# DCDC_2_Rev2.net
KiCad netlist of a schematic drawn in Altium Designer
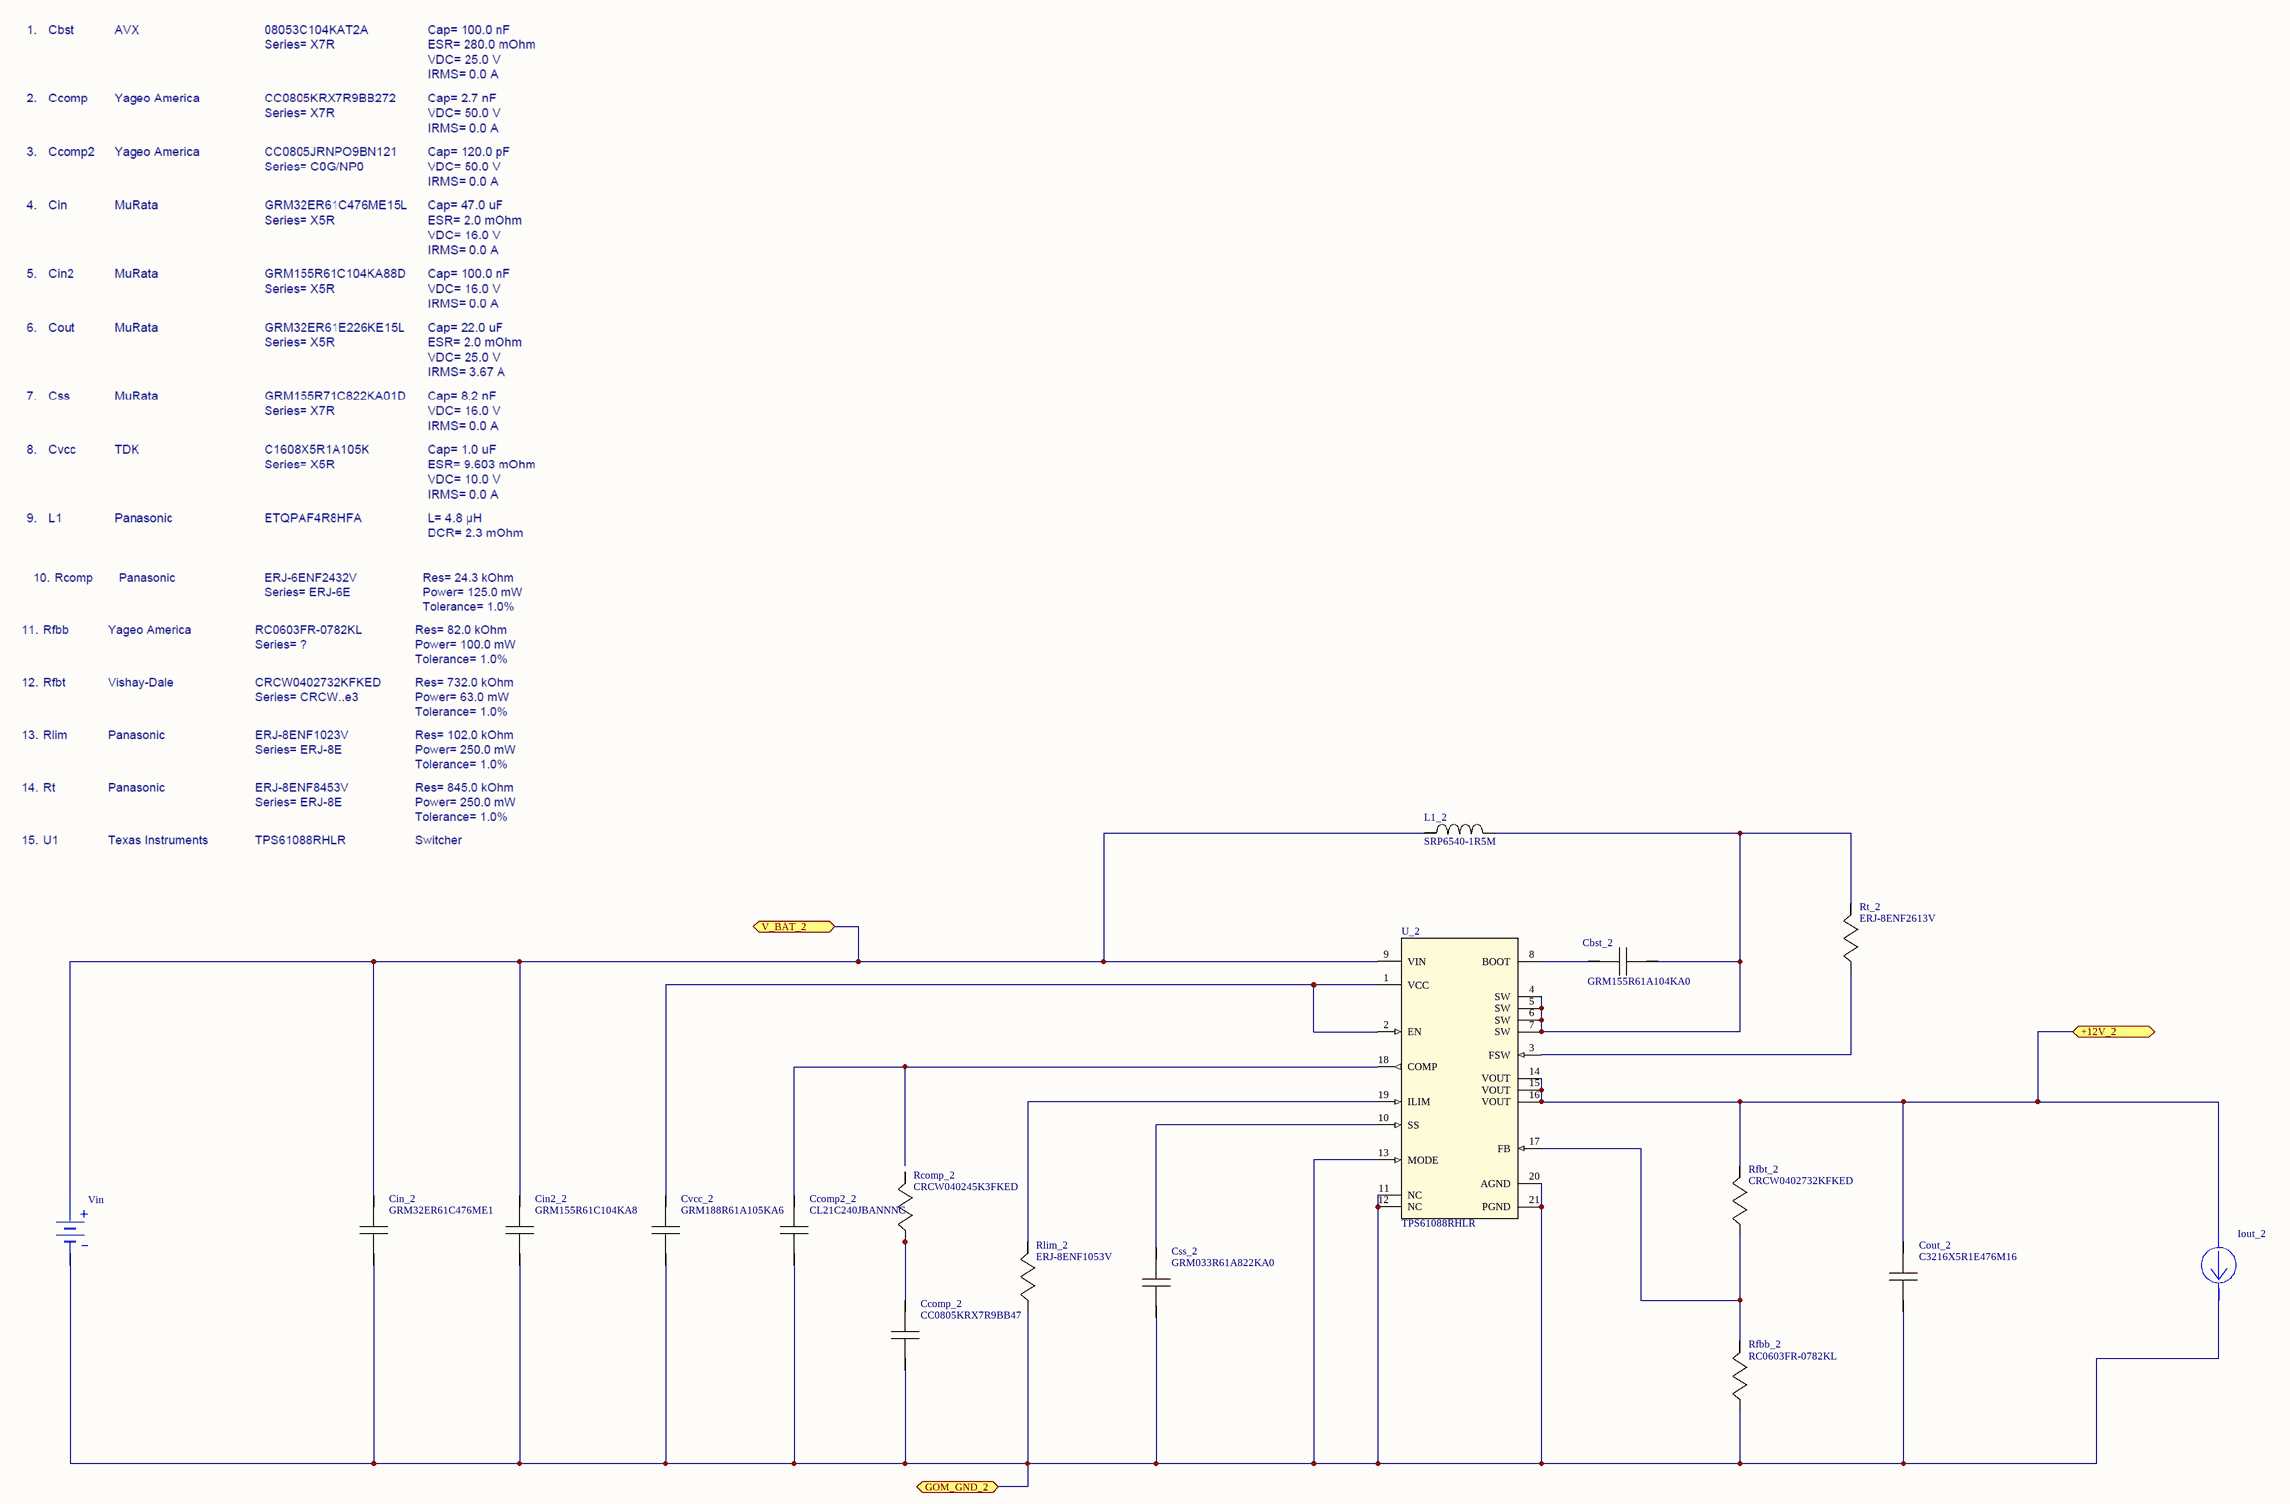
[diagram p0: DCDC_2_Rev2.SchDoc]

(export (version "E")
  (design (tool "Eeschema 10.0.6"))
  (components
    (comp (ref "Cbst_2")
      (value "GRM155R61A104KA0")
      (footprint "0402")
      (description "Imported")
      (fields (field (name "MANUFACTURER_PART_NUMBER") "GRM155R61A104KA01D"))
      (libsource (lib "2016-03-14_16-10-16") (part "GRM155R61A104KA0"))
    )
    (comp (ref "Ccomp2_2")
      (value "CL21C240JBANNNC")
      (footprint "0805")
      (description "Imported")
      (libsource (lib "2016-03-14_16-10-16") (part "CL21C240JBANNNC"))
    )
    (comp (ref "Ccomp_2")
      (value "CC0805KRX7R9BB47")
      (footprint "0805")
      (description "Imported")
      (fields (field (name "MANUFACTURER_PART_NUMBER") "CC0805KRX7R9BB471"))
      (libsource (lib "2016-03-14_16-10-16") (part "CC0805KRX7R9BB47"))
    )
    (comp (ref "Cin2_2")
      (value "GRM155R61C104KA8")
      (footprint "0402")
      (description "Imported")
      (fields (field (name "MANUFACTURER_PART_NUMBER") "GRM155R61C104KA88D"))
      (libsource (lib "2016-03-14_16-10-16") (part "GRM155R61C104KA8"))
    )
    (comp (ref "Cin_2")
      (value "GRM32ER61C476ME1")
      (footprint "1210_280")
      (description "Imported")
      (fields (field (name "MANUFACTURER_PART_NUMBER") "GRM32ER61C476ME15L"))
      (libsource (lib "2016-03-14_16-10-16") (part "GRM32ER61C476ME1"))
    )
    (comp (ref "Cout_2")
      (value "C3216X5R1E476M16")
      (footprint "1206_190")
      (description "Imported")
      (fields (field (name "MANUFACTURER_PART_NUMBER") "C3216X5R1E476M160AC"))
      (libsource (lib "2016-03-14_16-10-16") (part "C3216X5R1E476M16"))
    )
    (comp (ref "Css_2")
      (value "GRM033R61A822KA0")
      (footprint "0201")
      (description "Imported")
      (fields (field (name "MANUFACTURER_PART_NUMBER") "GRM033R61A822KA01D"))
      (libsource (lib "2016-03-14_16-10-16") (part "GRM033R61A822KA0"))
    )
    (comp (ref "Cvcc_2")
      (value "GRM188R61A105KA6")
      (footprint "0603")
      (description "Imported")
      (fields (field (name "MANUFACTURER_PART_NUMBER") "GRM188R61A105KA61D"))
      (libsource (lib "2016-03-14_16-10-16") (part "GRM188R61A105KA6"))
    )
    (comp (ref "Iout_2") (value "WB_CURRENT_LOAD") (libsource (lib "TI WEBENCH") (part "Iout")))
    (comp (ref "L1_2")
      (value "SRP6540-1R5M")
      (footprint "SRP6540")
      (description "Imported")
      (fields (field (name "MANUFACTURER") "Bourns"))
      (libsource (lib "2016-03-14_16-10-16") (part "SRP6540-1R5M"))
    )
    (comp (ref "Rcomp_2")
      (value "CRCW040245K3FKED")
      (footprint "0402")
      (description "Imported")
      (libsource (lib "2016-03-14_16-10-16") (part "CRCW040245K3FKED"))
    )
    (comp (ref "Rfbb_2")
      (value "RC0603FR-0782KL")
      (footprint "0603")
      (description "Imported")
      (libsource (lib "2016-03-14_16-10-16") (part "RC0603FR-0782KL"))
    )
    (comp (ref "Rfbt_2")
      (value "CRCW0402732KFKED")
      (footprint "0402")
      (description "Imported")
      (libsource (lib "2016-03-14_16-10-16") (part "CRCW0402732KFKED"))
    )
    (comp (ref "Rlim_2")
      (value "ERJ-8ENF1053V")
      (footprint "1206")
      (description "Imported")
      (libsource (lib "2016-03-14_16-10-16") (part "ERJ-8ENF1053V"))
    )
    (comp (ref "Rt_2")
      (value "ERJ-8ENF2613V")
      (footprint "1206")
      (description "Imported")
      (libsource (lib "2016-03-14_16-10-16") (part "ERJ-8ENF2613V"))
    )
    (comp (ref "U_2")
      (value "TPS61088RHLR")
      (footprint "RHL0020A")
      (description "Imported")
      (fields
        (field (name "ALTERNATE PARTNUMBER") "TPS61088RHLT")
        (field (name "MANUFACTURER") "Texas Instruments")
      )
      (libsource (lib "2016-03-14_16-10-16") (part "TPS61088RHLR"))
    )
    (comp (ref "Vin") (value "WB_BATTERY") (libsource (lib "TI WEBENCH") (part "Vin")))
  )
  (nets
    (net (code "1") (name "/+12V_2") (class "Default")
      (node (ref "Cout_2") (pin "1") (pinfunction "1_1") (pintype "passive"))
      (node (ref "Iout_2") (pin "1") (pinfunction "+_1") (pintype "passive"))
      (node (ref "Rfbt_2") (pin "1") (pinfunction "1_1") (pintype "passive"))
      (node (ref "U_2") (pin "14") (pinfunction "VOUT_14") (pintype "power_in"))
      (node (ref "U_2") (pin "15") (pinfunction "VOUT_15") (pintype "power_in"))
      (node (ref "U_2") (pin "16") (pinfunction "VOUT_16") (pintype "power_in"))
    )
    (net (code "2") (name "/GOM_GND_2") (class "Default")
      (node (ref "Ccomp2_2") (pin "2") (pinfunction "2_2") (pintype "passive"))
      (node (ref "Ccomp_2") (pin "2") (pinfunction "2_2") (pintype "passive"))
      (node (ref "Cin2_2") (pin "2") (pinfunction "2_2") (pintype "passive"))
      (node (ref "Cin_2") (pin "2") (pinfunction "2_2") (pintype "passive"))
      (node (ref "Cout_2") (pin "2") (pinfunction "2_2") (pintype "passive"))
      (node (ref "Css_2") (pin "2") (pinfunction "2_2") (pintype "passive"))
      (node (ref "Cvcc_2") (pin "2") (pinfunction "2_2") (pintype "passive"))
      (node (ref "Iout_2") (pin "2") (pinfunction "-_2") (pintype "passive"))
      (node (ref "Rfbb_2") (pin "2") (pinfunction "2_2") (pintype "passive"))
      (node (ref "Rlim_2") (pin "2") (pinfunction "2_2") (pintype "passive"))
      (node (ref "U_2") (pin "11") (pinfunction "NC_11") (pintype "passive"))
      (node (ref "U_2") (pin "12") (pinfunction "NC_12") (pintype "passive"))
      (node (ref "U_2") (pin "13") (pinfunction "MODE_13") (pintype "input"))
      (node (ref "U_2") (pin "20") (pinfunction "AGND_20") (pintype "power_in"))
      (node (ref "U_2") (pin "21") (pinfunction "PGND_21") (pintype "power_in"))
      (node (ref "Vin") (pin "2") (pinfunction "-_2") (pintype "passive"))
    )
    (net (code "3") (name "/V_BAT_2") (class "Default")
      (node (ref "Cin2_2") (pin "1") (pinfunction "1_1") (pintype "passive"))
      (node (ref "Cin_2") (pin "1") (pinfunction "1_1") (pintype "passive"))
      (node (ref "L1_2") (pin "1") (pinfunction "1_1") (pintype "passive"))
      (node (ref "U_2") (pin "9") (pinfunction "VIN_9") (pintype "power_in"))
      (node (ref "Vin") (pin "1") (pinfunction "+_1") (pintype "passive"))
    )
    (net (code "4") (name "Net-(Cbst_2-Pad1)") (class "Default")
      (node (ref "Cbst_2") (pin "1") (pinfunction "1_1") (pintype "passive"))
      (node (ref "L1_2") (pin "2") (pinfunction "2_2") (pintype "passive"))
      (node (ref "Rt_2") (pin "1") (pinfunction "1_1") (pintype "passive"))
      (node (ref "U_2") (pin "4") (pinfunction "SW_4") (pintype "power_in"))
      (node (ref "U_2") (pin "5") (pinfunction "SW_5") (pintype "power_in"))
      (node (ref "U_2") (pin "6") (pinfunction "SW_6") (pintype "power_in"))
      (node (ref "U_2") (pin "7") (pinfunction "SW_7") (pintype "power_in"))
    )
    (net (code "5") (name "Net-(Ccomp_2-Pad1)") (class "Default")
      (node (ref "Ccomp_2") (pin "1") (pinfunction "1_1") (pintype "passive"))
      (node (ref "Rcomp_2") (pin "2") (pinfunction "2_2") (pintype "passive"))
    )
    (net (code "6") (name "Net-(U_2-BOOT)") (class "Default")
      (node (ref "Cbst_2") (pin "2") (pinfunction "2_2") (pintype "passive"))
      (node (ref "U_2") (pin "8") (pinfunction "BOOT_8") (pintype "power_in"))
    )
    (net (code "7") (name "Net-(U_2-COMP)") (class "Default")
      (node (ref "Ccomp2_2") (pin "1") (pinfunction "1_1") (pintype "passive"))
      (node (ref "U_2") (pin "18") (pinfunction "COMP_18") (pintype "output"))
    )
    (net (code "8") (name "Net-(U_2-EN)") (class "Default")
      (node (ref "Cvcc_2") (pin "1") (pinfunction "1_1") (pintype "passive"))
      (node (ref "U_2") (pin "1") (pinfunction "VCC_1") (pintype "power_in"))
      (node (ref "U_2") (pin "2") (pinfunction "EN_2") (pintype "input"))
    )
    (net (code "9") (name "Net-(U_2-FB)") (class "Default")
      (node (ref "Rfbb_2") (pin "1") (pinfunction "1_1") (pintype "passive"))
      (node (ref "Rfbt_2") (pin "2") (pinfunction "2_2") (pintype "passive"))
      (node (ref "U_2") (pin "17") (pinfunction "FB_17") (pintype "input"))
    )
    (net (code "10") (name "Net-(U_2-FSW)") (class "Default")
      (node (ref "Rt_2") (pin "2") (pinfunction "2_2") (pintype "passive"))
      (node (ref "U_2") (pin "3") (pinfunction "FSW_3") (pintype "input"))
    )
    (net (code "11") (name "Net-(U_2-ILIM)") (class "Default")
      (node (ref "Rlim_2") (pin "1") (pinfunction "1_1") (pintype "passive"))
      (node (ref "U_2") (pin "19") (pinfunction "ILIM_19") (pintype "input"))
    )
    (net (code "12") (name "Net-(U_2-SS)") (class "Default")
      (node (ref "Css_2") (pin "1") (pinfunction "1_1") (pintype "passive"))
      (node (ref "U_2") (pin "10") (pinfunction "SS_10") (pintype "input"))
    )
    (net (code "13") (name "unconnected-(Rcomp_2-Pad1)") (class "Default")
      (node (ref "Rcomp_2") (pin "1") (pinfunction "1_1") (pintype "passive"))
    )
  )
)
